# Gastroscopy-Tool-Sensor_TOF.net
KiCad netlist of a schematic drawn in Altium Designer
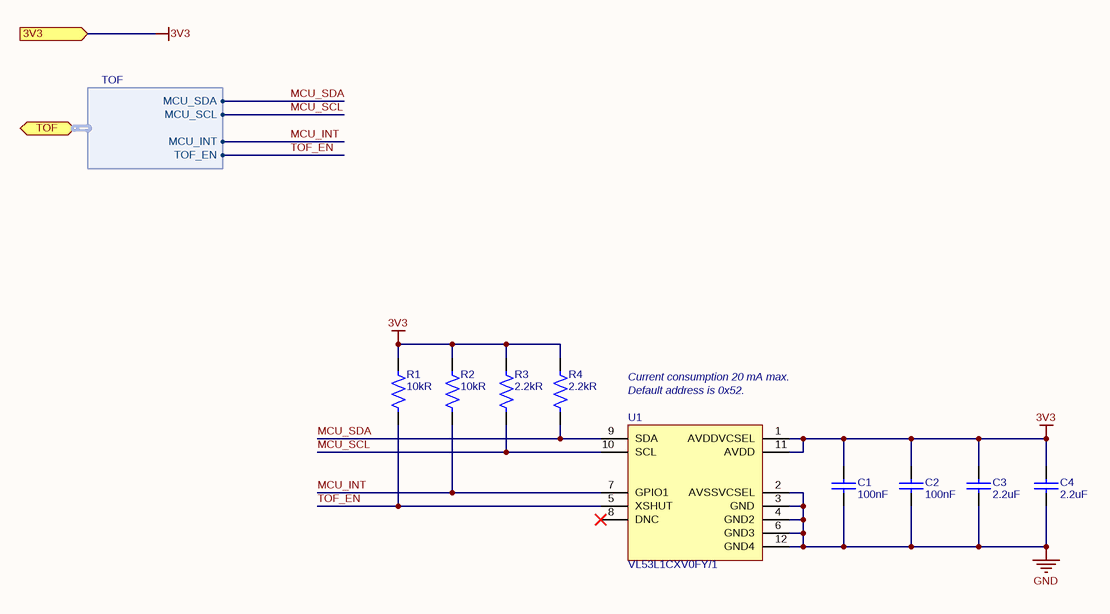
[diagram p0: Gastroscopy-Tool-Sensor_TOF.SchDoc]

(export (version "E")
  (design (tool "Eeschema 10.0.6"))
  (components
    (comp (ref "C1")
      (value "100nF")
      (footprint "CAP_0402")
      (description "CAP CER 0.1UF 25V X7R 0402")
      (fields
        (field (name "MANUFACTURER") "Yageo")
        (field (name "MANUFACTURER PART NUMBER") "CC0402JRX7R8BB104")
      )
      (libsource (lib "Gastroscopy-Tool") (part "CC0402JRX7R8BB104"))
    )
    (comp (ref "C2")
      (value "100nF")
      (footprint "CAP_0402")
      (description "CAP CER 0.1UF 25V X7R 0402")
      (fields
        (field (name "MANUFACTURER") "Yageo")
        (field (name "MANUFACTURER PART NUMBER") "CC0402JRX7R8BB104")
      )
      (libsource (lib "Gastroscopy-Tool") (part "CC0402JRX7R8BB104"))
    )
    (comp (ref "C3")
      (value "2.2uF")
      (footprint "CAP_0402")
      (description "CAP CER 2.2UF 10V X7R 0402")
      (fields
        (field (name "MANUFACTURER") "Murata")
        (field (name "MANUFACTURER PART NUMBER") "GRM155Z71A225KE44D")
      )
      (libsource (lib "Gastroscopy-Tool") (part "GRM155Z71A225KE44D"))
    )
    (comp (ref "C4")
      (value "2.2uF")
      (footprint "CAP_0402")
      (description "CAP CER 2.2UF 10V X7R 0402")
      (fields
        (field (name "MANUFACTURER") "Murata")
        (field (name "MANUFACTURER PART NUMBER") "GRM155Z71A225KE44D")
      )
      (libsource (lib "Gastroscopy-Tool") (part "GRM155Z71A225KE44D"))
    )
    (comp (ref "R1")
      (value "10kR")
      (footprint "RES_0402")
      (description "RES 10K OHM 1% 1/16W 0402")
      (fields
        (field (name "MANUFACTURER") "Yageo")
        (field (name "MANUFACTURER PART NUMBER") "RC0402FR-0710KL")
      )
      (libsource (lib "Gastroscopy-Tool") (part "RC0402FR-0710KL"))
    )
    (comp (ref "R2")
      (value "10kR")
      (footprint "RES_0402")
      (description "RES 10K OHM 1% 1/16W 0402")
      (fields
        (field (name "MANUFACTURER") "Yageo")
        (field (name "MANUFACTURER PART NUMBER") "RC0402FR-0710KL")
      )
      (libsource (lib "Gastroscopy-Tool") (part "RC0402FR-0710KL"))
    )
    (comp (ref "R3")
      (value "2.2kR")
      (footprint "RES_0402")
      (description "RES 2.2K OHM 1% 1/16W 0402")
      (fields
        (field (name "MANUFACTURER") "Yageo")
        (field (name "MANUFACTURER PART NUMBER") "RC0402FR-072K2L")
      )
      (libsource (lib "Gastroscopy-Tool") (part "RC0402FR-072K2L"))
    )
    (comp (ref "R4")
      (value "2.2kR")
      (footprint "RES_0402")
      (description "RES 2.2K OHM 1% 1/16W 0402")
      (fields
        (field (name "MANUFACTURER") "Yageo")
        (field (name "MANUFACTURER PART NUMBER") "RC0402FR-072K2L")
      )
      (libsource (lib "Gastroscopy-Tool") (part "RC0402FR-072K2L"))
    )
    (comp (ref "U1")
      (value "VL53L1CXV0FY/1")
      (footprint "VL53L1CXV0FY/1")
      (description "SENSOR OPTICAL 4M I2C")
      (libsource (lib "Gastroscopy-Tool") (part "VL53L1CXV0FY/1"))
    )
  )
  (nets
    (net (code "2") (name "/MCU_INT") (class "Default")
      (node (ref "R2") (pin "2") (pinfunction "2_2") (pintype "passive"))
      (node (ref "U1") (pin "7") (pinfunction "GPIO1_7") (pintype "passive"))
    )
    (net (code "3") (name "/MCU_SCL") (class "Default")
      (node (ref "R3") (pin "2") (pinfunction "2_2") (pintype "passive"))
      (node (ref "U1") (pin "10") (pinfunction "SCL_10") (pintype "passive"))
    )
    (net (code "4") (name "/MCU_SDA") (class "Default")
      (node (ref "R4") (pin "2") (pinfunction "2_2") (pintype "passive"))
      (node (ref "U1") (pin "9") (pinfunction "SDA_9") (pintype "passive"))
    )
    (net (code "5") (name "/TOF_EN") (class "Default")
      (node (ref "R1") (pin "2") (pinfunction "2_2") (pintype "passive"))
      (node (ref "U1") (pin "5") (pinfunction "XSHUT_5") (pintype "passive"))
    )
    (net (code "7") (name "3V3") (class "Default")
      (node (ref "C1") (pin "2") (pinfunction "2_2") (pintype "passive"))
      (node (ref "C2") (pin "2") (pinfunction "2_2") (pintype "passive"))
      (node (ref "C3") (pin "2") (pinfunction "2_2") (pintype "passive"))
      (node (ref "C4") (pin "2") (pinfunction "2_2") (pintype "passive"))
      (node (ref "R1") (pin "1") (pinfunction "1_1") (pintype "passive"))
      (node (ref "R2") (pin "1") (pinfunction "1_1") (pintype "passive"))
      (node (ref "R3") (pin "1") (pinfunction "1_1") (pintype "passive"))
      (node (ref "R4") (pin "1") (pinfunction "1_1") (pintype "passive"))
      (node (ref "U1") (pin "1") (pinfunction "AVDDVCSEL_1") (pintype "passive"))
      (node (ref "U1") (pin "11") (pinfunction "AVDD_11") (pintype "passive"))
    )
    (net (code "8") (name "GND") (class "Default")
      (node (ref "C1") (pin "1") (pinfunction "1_1") (pintype "passive"))
      (node (ref "C2") (pin "1") (pinfunction "1_1") (pintype "passive"))
      (node (ref "C3") (pin "1") (pinfunction "1_1") (pintype "passive"))
      (node (ref "C4") (pin "1") (pinfunction "1_1") (pintype "passive"))
      (node (ref "U1") (pin "12") (pinfunction "GND4_12") (pintype "passive"))
      (node (ref "U1") (pin "2") (pinfunction "AVSSVCSEL_2") (pintype "passive"))
      (node (ref "U1") (pin "3") (pinfunction "GND_3") (pintype "passive"))
      (node (ref "U1") (pin "4") (pinfunction "GND2_4") (pintype "passive"))
      (node (ref "U1") (pin "6") (pinfunction "GND3_6") (pintype "passive"))
    )
    (net (code "9") (name "unconnected-(U1-DNC-Pad8)") (class "Default")
      (node (ref "U1") (pin "8") (pinfunction "DNC_8") (pintype "passive+no_connect"))
    )
  )
)
